# 06_nRF52840_Analog.net
KiCad netlist of a schematic drawn in Altium Designer
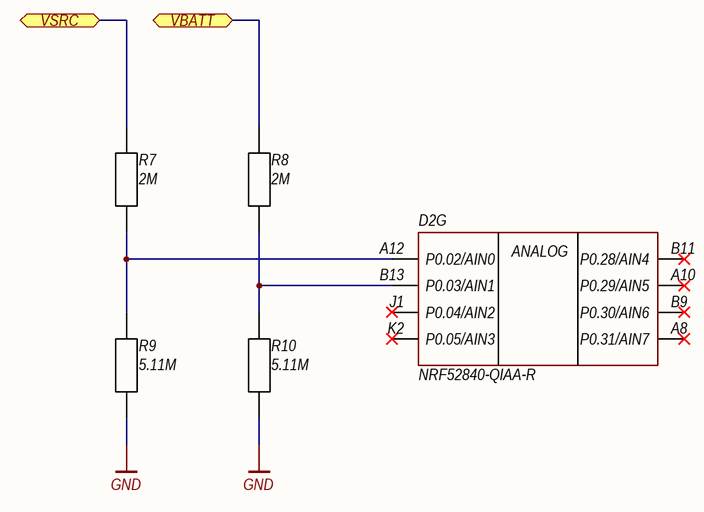
[diagram p0: 06_nRF52840_Analog.SchDoc]

(export (version "E")
  (design (tool "Eeschema 10.0.6"))
  (components
    (comp (ref "D2")
      (value "NRF52840-QIAA-R")
      (footprint "AQFN50P700X700X85_HS-74N")
      (description "IC RF TxRx + MCU 802.15.4, Bluetooth Bluetooth v5.0 2.4GHz 73-VFQFN Dual Rows, Exposed Pad")
      (fields (field (name "MANUFACTURER") "Nordic Semiconductor ASA"))
      (libsource (lib "Node01") (part "nRF52840-QFN373"))
    )
    (comp (ref "R7")
      (value "2M")
      (footprint "RESC1608X05N")
      (description "SMD resistor")
      (fields (field (name "MANUFACTURER") "Yageo") (field (name "PARTNUMBER") "RC0603JR-072ML"))
      (libsource (lib "Node01") (part "resistor_smd"))
    )
    (comp (ref "R8")
      (value "2M")
      (footprint "RESC1608X05N")
      (description "SMD resistor")
      (fields (field (name "MANUFACTURER") "Yageo") (field (name "PARTNUMBER") "RC0603JR-072ML"))
      (libsource (lib "Node01") (part "resistor_smd"))
    )
    (comp (ref "R9")
      (value "5.11M")
      (footprint "RESC1608X05N")
      (description "SMD resistor")
      (fields (field (name "MANUFACTURER") "Yageo") (field (name "PARTNUMBER") "RC0603FR-075M11L"))
      (libsource (lib "Node01") (part "resistor_smd"))
    )
    (comp (ref "R10")
      (value "5.11M")
      (footprint "RESC1608X05N")
      (description "SMD resistor")
      (fields (field (name "MANUFACTURER") "Yageo") (field (name "PARTNUMBER") "RC0603FR-075M11L"))
      (libsource (lib "Node01") (part "resistor_smd"))
    )
  )
  (nets
    (net (code "1") (name "/VBATT") (class "Default")
      (node (ref "R8") (pin "2") (pinfunction "2_2") (pintype "power_in"))
    )
    (net (code "2") (name "/VSRC") (class "Default")
      (node (ref "R7") (pin "2") (pinfunction "2_2") (pintype "power_in"))
    )
    (net (code "3") (name "GND") (class "Default")
      (node (ref "R10") (pin "1") (pinfunction "1_1") (pintype "power_in"))
      (node (ref "R9") (pin "1") (pinfunction "1_1") (pintype "power_in"))
    )
    (net (code "4") (name "Net-(D2G-P0.02{slash}AIN0)") (class "Default")
      (node (ref "D2") (pin "A12") (pinfunction "P0.02/AIN0_A12") (pintype "power_in"))
      (node (ref "R7") (pin "1") (pinfunction "1_1") (pintype "power_in"))
      (node (ref "R9") (pin "2") (pinfunction "2_2") (pintype "power_in"))
    )
    (net (code "5") (name "Net-(D2G-P0.03{slash}AIN1)") (class "Default")
      (node (ref "D2") (pin "B13") (pinfunction "P0.03/AIN1_B13") (pintype "power_in"))
      (node (ref "R10") (pin "2") (pinfunction "2_2") (pintype "power_in"))
      (node (ref "R8") (pin "1") (pinfunction "1_1") (pintype "power_in"))
    )
    (net (code "6") (name "unconnected-(D2G-P0.04{slash}AIN2-PadJ1)") (class "Default")
      (node (ref "D2") (pin "J1") (pinfunction "P0.04/AIN2_J1") (pintype "power_in+no_connect"))
    )
    (net (code "7") (name "unconnected-(D2G-P0.05{slash}AIN3-PadK2)") (class "Default")
      (node (ref "D2") (pin "K2") (pinfunction "P0.05/AIN3_K2") (pintype "power_in+no_connect"))
    )
    (net (code "8") (name "unconnected-(D2G-P0.28{slash}AIN4-PadB11)") (class "Default")
      (node (ref "D2") (pin "B11") (pinfunction "P0.28/AIN4_B11") (pintype "power_in+no_connect"))
    )
    (net (code "9") (name "unconnected-(D2G-P0.29{slash}AIN5-PadA10)") (class "Default")
      (node (ref "D2") (pin "A10") (pinfunction "P0.29/AIN5_A10") (pintype "power_in+no_connect"))
    )
    (net (code "10") (name "unconnected-(D2G-P0.30{slash}AIN6-PadB9)") (class "Default")
      (node (ref "D2") (pin "B9") (pinfunction "P0.30/AIN6_B9") (pintype "power_in+no_connect"))
    )
    (net (code "11") (name "unconnected-(D2G-P0.31{slash}AIN7-PadA8)") (class "Default")
      (node (ref "D2") (pin "A8") (pinfunction "P0.31/AIN7_A8") (pintype "power_in+no_connect"))
    )
  )
)
